# STM32_Sheet.net
KiCad netlist of a schematic drawn in Altium Designer
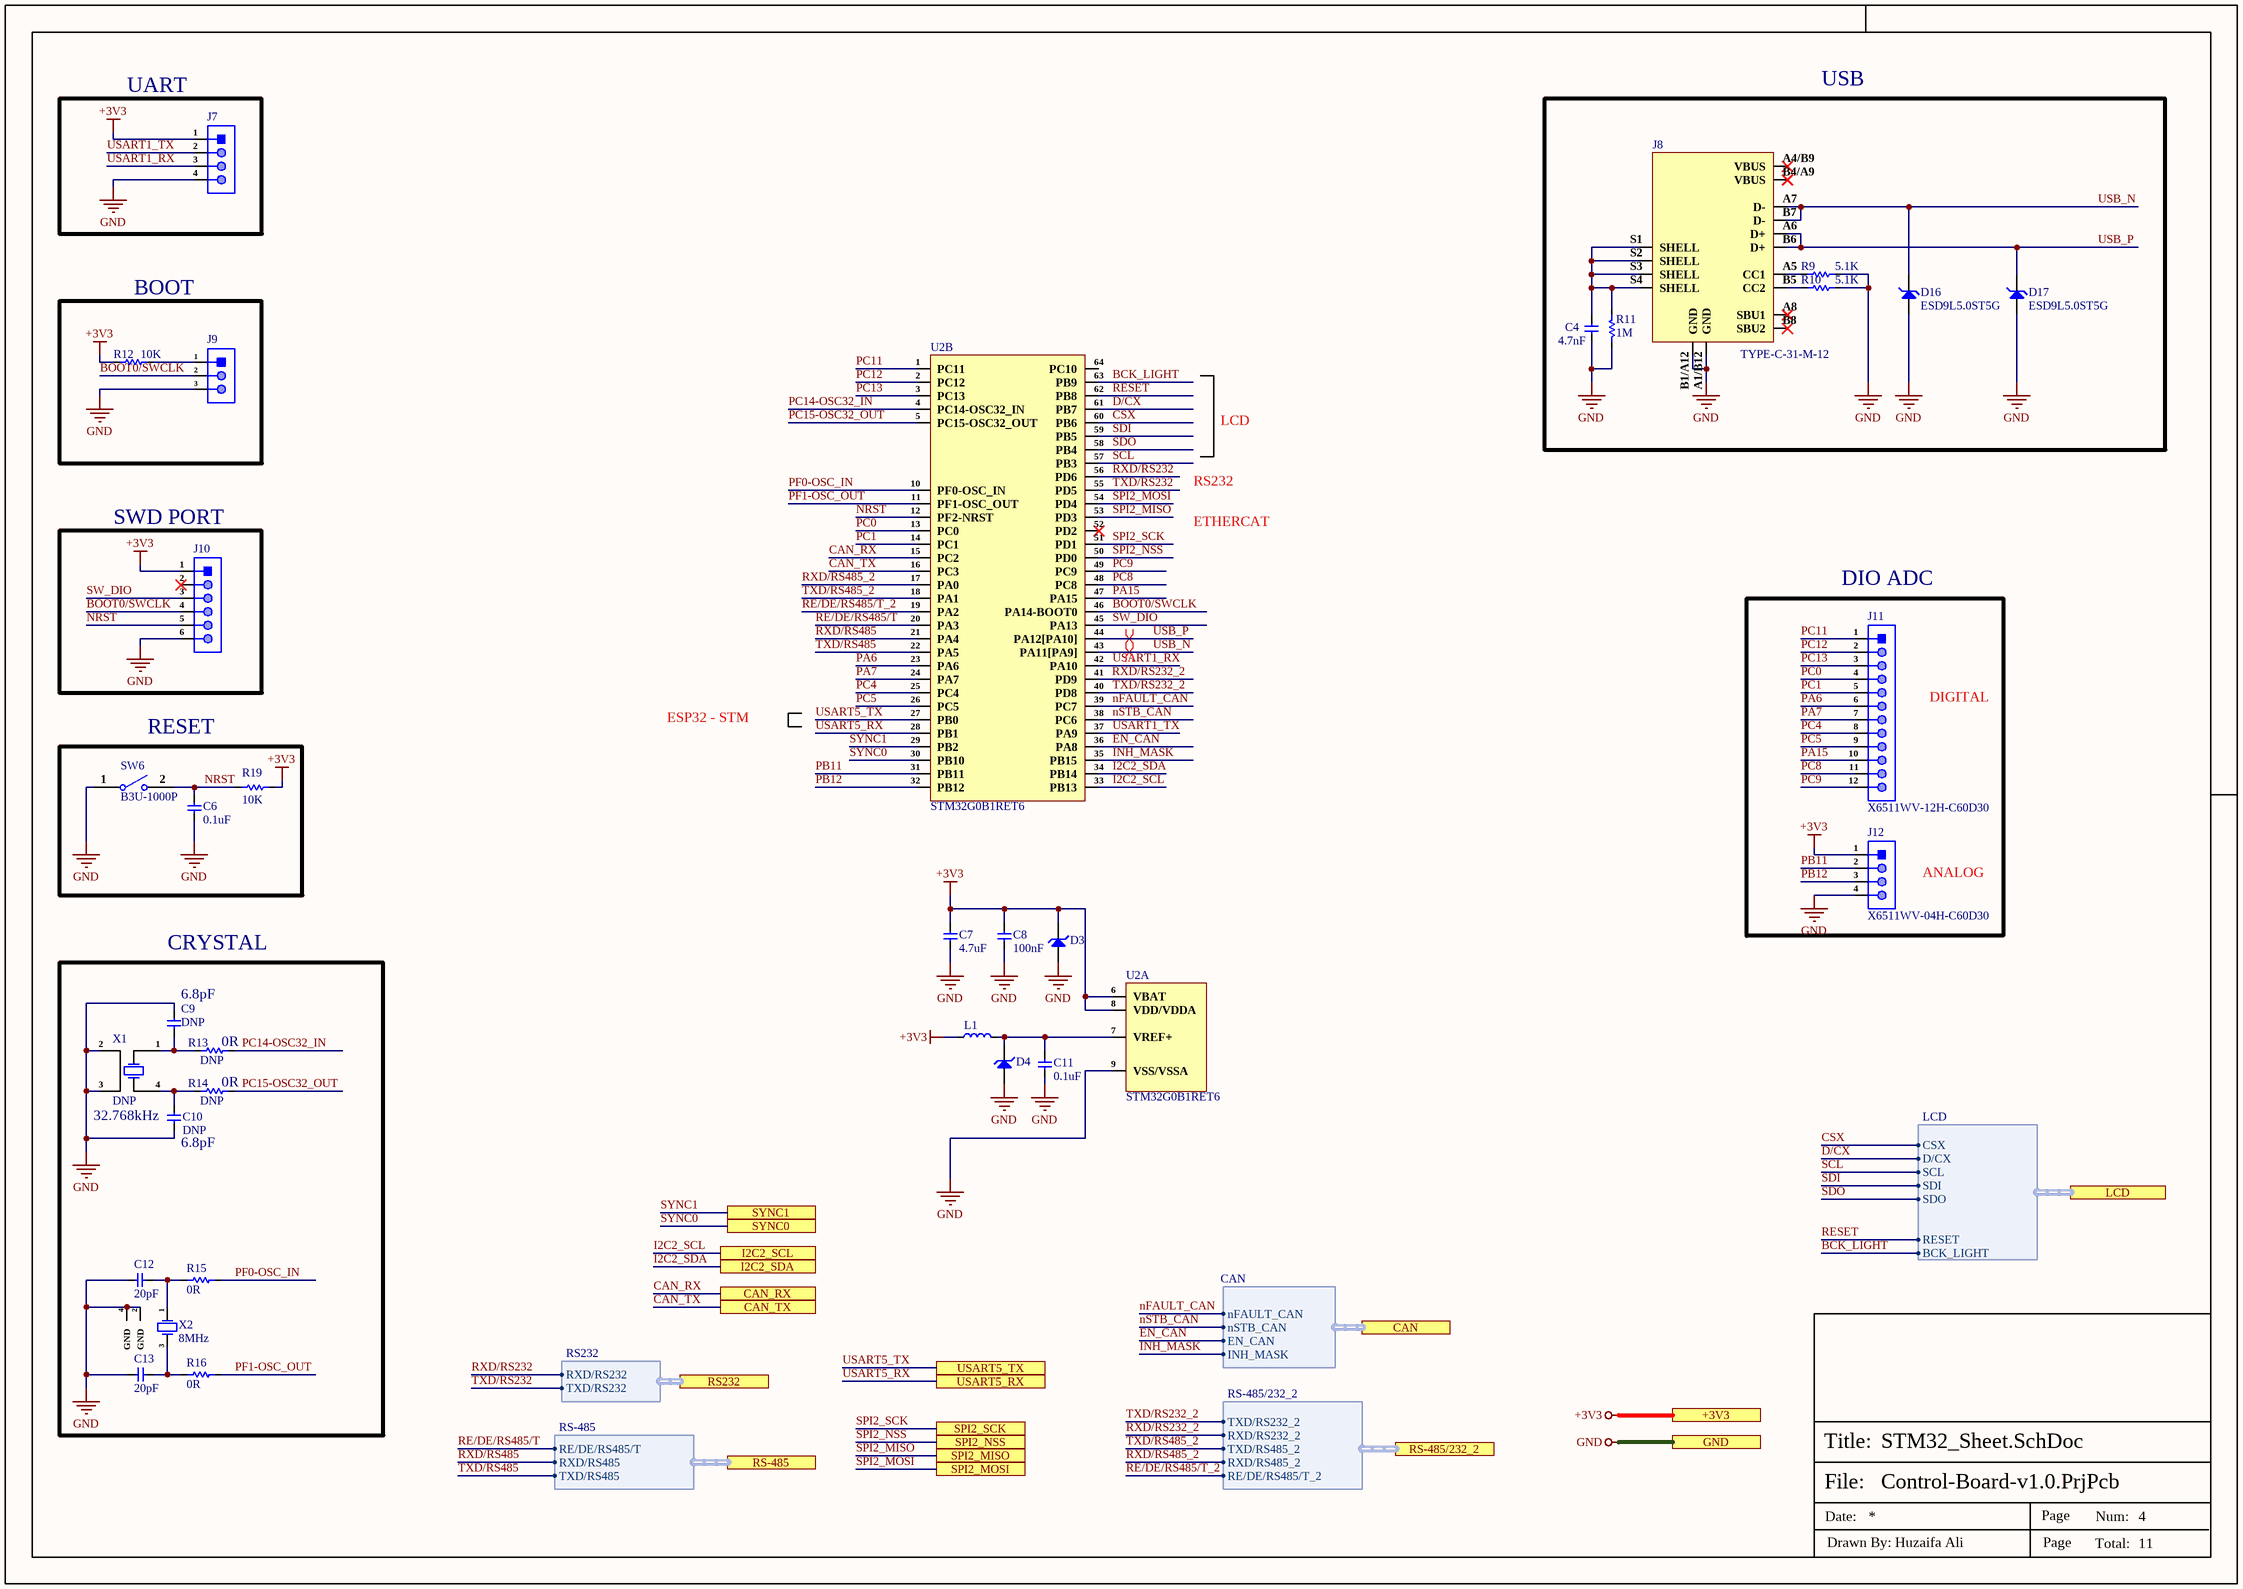
[diagram p0: STM32_Sheet.SchDoc]

(export (version "E")
  (design (tool "Eeschema 10.0.6"))
  (components
    (comp (ref "C4")
      (value "4.7nF")
      (footprint "Cap-0603")
      (description "CAP CER 4700PF 50V C0G/NPO 0603")
      (fields
        (field (name "MANUFACTURER") "Yageo")
        (field (name "MANUFACTURER PART NUMBER") "CC0603JRNPO9BN472")
      )
      (libsource (lib "eSpark_centralized_Library(2022)") (part "CC0603JRNPO9BN472"))
    )
    (comp (ref "C6")
      (value "0.1uF")
      (footprint "Cap-0402")
      (description "CAP CER 0.1UF 16V X7R 0402")
      (fields
        (field (name "MANUFACTURER") "Yageo")
        (field (name "MANUFACTURER PART NUMBER") "CC0402JRX7R7BB104")
      )
      (libsource (lib "eSpark Libraries") (part "CC0402JRX7R7BB104"))
    )
    (comp (ref "C7")
      (value "4.7uF")
      (footprint "Cap-0402")
      (description "CAP CER 4.7UF 10V X5R 0402")
      (fields
        (field (name "MANUFACTURER") "Yageo")
        (field (name "MANUFACTURER PART NUMBER") "CC0402KRX5R6BB475")
      )
      (libsource (lib "eSpark Libraries") (part "CC0402KRX5R6BB475"))
    )
    (comp (ref "C8")
      (value "100nF")
      (footprint "cap-0402")
      (description "CAP CER 0.1UF 50V X7R 0402")
      (fields
        (field (name "MANUFACTURER") "TDK")
        (field (name "MANUFACTURER PART NUMBER") "C1005X7R1H104KT000F")
      )
      (libsource (lib "eSpark Libraries") (part "C1005X7R1H104KT000F"))
    )
    (comp (ref "C9")
      (value "DNP")
      (footprint "Cap-0402")
      (description "CAP CER 6.8PF 50V C0G/NPO 0402")
      (fields
        (field (name "MANUFACTURER") "Yageo")
        (field (name "MANUFACTURER PART NUMBER") "CC0402CRNPO9BN6R8")
      )
      (libsource (lib "eSpark Libraries") (part "CC0402CRNPO9BN6R8"))
    )
    (comp (ref "C10")
      (value "DNP")
      (footprint "Cap-0402")
      (description "CAP CER 6.8PF 50V C0G/NPO 0402")
      (fields
        (field (name "MANUFACTURER") "Yageo")
        (field (name "MANUFACTURER PART NUMBER") "CC0402CRNPO9BN6R8")
      )
      (libsource (lib "eSpark Libraries") (part "CC0402CRNPO9BN6R8"))
    )
    (comp (ref "C11")
      (value "0.1uF")
      (footprint "Cap-0402")
      (description "CAP CER 0.1UF 16V X7R 0402")
      (fields
        (field (name "MANUFACTURER") "Yageo")
        (field (name "MANUFACTURER PART NUMBER") "CC0402JRX7R7BB104")
      )
      (libsource (lib "eSpark Libraries") (part "CC0402JRX7R7BB104"))
    )
    (comp (ref "C12")
      (value "20pF")
      (footprint "Cap-0402")
      (description "CAP CER 20PF 50V C0G/NPO 0402")
      (fields (field (name "LCSC PART NUMBER") "C107000") (field (name "MANUFACTURER") "Yageo"))
      (libsource (lib "eSpark Libraries") (part "CC0402JRNPO9BN200"))
    )
    (comp (ref "C13")
      (value "20pF")
      (footprint "Cap-0402")
      (description "CAP CER 20PF 50V C0G/NPO 0402")
      (fields (field (name "LCSC PART NUMBER") "C107000") (field (name "MANUFACTURER") "Yageo"))
      (libsource (lib "eSpark Libraries") (part "CC0402JRNPO9BN200"))
    )
    (comp (ref "D3")
      (value "AZ3003-01G")
      (footprint "SOD-123")
      (description "TVS SURGE PROTECTOR 1-CH 3.3V")
      (fields (field (name "MANUFACTURER") "Amazing"))
      (libsource (lib "eSpark Libraries") (part "AZ3003-01G"))
    )
    (comp (ref "D4")
      (value "AZ3003-01G")
      (footprint "SOD-123")
      (description "TVS SURGE PROTECTOR 1-CH 3.3V")
      (fields (field (name "MANUFACTURER") "Amazing"))
      (libsource (lib "eSpark Libraries") (part "AZ3003-01G"))
    )
    (comp (ref "D16")
      (value "ESD9L5.0ST5G")
      (footprint "SOD-923.")
      (description "TVS DIODE 5V 9.8V SOD923")
      (fields (field (name "MANUFACTURER") "ON Semiconductor") (field (name "LCSC PART NUMBER") "C82326"))
      (libsource (lib "eSpark Libraries") (part "ESD9L5.0ST5G"))
    )
    (comp (ref "D17")
      (value "ESD9L5.0ST5G")
      (footprint "SOD-923.")
      (description "TVS DIODE 5V 9.8V SOD923")
      (fields (field (name "MANUFACTURER") "ON Semiconductor") (field (name "LCSC PART NUMBER") "C82326"))
      (libsource (lib "eSpark Libraries") (part "ESD9L5.0ST5G"))
    )
    (comp (ref "J7")
      (value "X6511WV-04H-C60D30")
      (footprint "HDR1X4_")
      (fields (field (name "MANUFACTURER") "XKB") (field (name "LCSC PART NUMBER") "C706876"))
      (libsource (lib "eSpark Libraries") (part "X6511WV-04H-C60D30"))
    )
    (comp (ref "J8")
      (value "TYPE-C-31-M-12")
      (footprint "TYPE-C-31-M-12_")
      (description "5A 1 16P Female Type-C SMD USB Connectors ROHS")
      (fields
        (field (name "MANUFACTURER") "Korean Hroparts Elec")
        (field (name "LCSC PART NUMBER") "C165948")
      )
      (libsource (lib "eSpark Libraries") (part "TYPE-C-31-M-12"))
    )
    (comp (ref "J9")
      (value "68000-103HLF")
      (footprint "HDR1X3_")
      (description "CONN HEADER VERT 3POS 2.54MM")
      (fields (field (name "LCSC PART NUMBER") "C168677"))
      (libsource (lib "eSpark Libraries") (part "68000-103HLF"))
    )
    (comp (ref "J10")
      (value "X6511WV-06H-C60D30")
      (footprint "HDR1X6_")
      (fields (field (name "MANUFACTURER") "XKB") (field (name "LCSC PART NUMBER") "C706878"))
      (libsource (lib "eSpark Libraries") (part "X6511WV-06H-C60D30"))
    )
    (comp (ref "J11")
      (value "X6511WV-12H-C60D30")
      (footprint "HDR 1x12 TH")
      (fields (field (name "MANUFACTURER") "XKB") (field (name "LCSC PART NUMBER") "C725944"))
      (libsource (lib "eSpark Libraries") (part "X6511WV-12H-C60D30"))
    )
    (comp (ref "J12")
      (value "X6511WV-04H-C60D30")
      (footprint "HDR1X4_")
      (fields (field (name "MANUFACTURER") "XKB") (field (name "LCSC PART NUMBER") "C706876"))
      (libsource (lib "eSpark Libraries") (part "X6511WV-04H-C60D30"))
    )
    (comp (ref "L1")
      (value "BLM15AG601SN1D")
      (footprint "IND-0402")
      (description "FERRITE BEAD 600 OHM 0402 1LN")
      (fields (field (name "MANUFACTURER") "Murata") (field (name "TOLERANCE") "25%"))
      (libsource (lib "eSpark Libraries") (part "BLM15AG601SN1D"))
    )
    (comp (ref "R9")
      (value "5.1K")
      (footprint "Res-0402")
      (description "RES 5.1K OHM 1% 1/16W 0402")
      (fields
        (field (name "MANUFACTURER") "Yageo")
        (field (name "MANUFACTURER PART NUMBER") "RC0402FR-075K1L")
      )
      (libsource (lib "eSpark Libraries") (part "RC0402FR-075K1L"))
    )
    (comp (ref "R10")
      (value "5.1K")
      (footprint "Res-0402")
      (description "RES 5.1K OHM 1% 1/16W 0402")
      (fields
        (field (name "MANUFACTURER") "Yageo")
        (field (name "MANUFACTURER PART NUMBER") "RC0402FR-075K1L")
      )
      (libsource (lib "eSpark Libraries") (part "RC0402FR-075K1L"))
    )
    (comp (ref "R11")
      (value "1M")
      (footprint "Res-0402")
      (description "RES SMD 1M OHM 5% 1/16W 0402")
      (fields
        (field (name "MANUFACTURER") "Yageo")
        (field (name "MANUFACTURER PART NUMBER") "AF0402JR-071ML")
      )
      (libsource (lib "eSpark_centralized_Library(2022)") (part "AF0402JR-071ML"))
    )
    (comp (ref "R12")
      (value "10K")
      (footprint "Res-0402")
      (description "RES 10K OHM 1% 1/16W 0402")
      (fields
        (field (name "MANUFACTURER") "Yageo")
        (field (name "MANUFACTURER PART NUMBER") "RC0402FR-0710KL")
      )
      (libsource (lib "eSpark Libraries") (part "RC0402FR-0710KL"))
    )
    (comp (ref "R13")
      (value "DNP")
      (footprint "Res-0603")
      (description "RES 0 OHM JUMPER 1/10W 0603")
      (fields
        (field (name "MANUFACTURER") "Yageo")
        (field (name "MANUFACTURER PART NUMBER") "RC0603JR-070RL")
      )
      (libsource (lib "eSpark Libraries") (part "RC0603JR-070RL"))
    )
    (comp (ref "R14")
      (value "DNP")
      (footprint "Res-0603")
      (description "RES 0 OHM JUMPER 1/10W 0603")
      (fields
        (field (name "MANUFACTURER") "Yageo")
        (field (name "MANUFACTURER PART NUMBER") "RC0603JR-070RL")
      )
      (libsource (lib "eSpark Libraries") (part "RC0603JR-070RL"))
    )
    (comp (ref "R15")
      (value "0R")
      (footprint "Res-0603")
      (description "RES 0 OHM JUMPER 1/10W 0603")
      (fields
        (field (name "MANUFACTURER") "Yageo")
        (field (name "MANUFACTURER PART NUMBER") "RC0603JR-070RL")
      )
      (libsource (lib "eSpark Libraries") (part "RC0603JR-070RL"))
    )
    (comp (ref "R16")
      (value "0R")
      (footprint "Res-0603")
      (description "RES 0 OHM JUMPER 1/10W 0603")
      (fields
        (field (name "MANUFACTURER") "Yageo")
        (field (name "MANUFACTURER PART NUMBER") "RC0603JR-070RL")
      )
      (libsource (lib "eSpark Libraries") (part "RC0603JR-070RL"))
    )
    (comp (ref "R19")
      (value "10K")
      (footprint "Res-0402")
      (description "RES 10K OHM 1% 1/16W 0402")
      (fields
        (field (name "MANUFACTURER") "Yageo")
        (field (name "MANUFACTURER PART NUMBER") "RC0402FR-0710KL")
      )
      (libsource (lib "eSpark Libraries") (part "RC0402FR-0710KL"))
    )
    (comp (ref "SW6")
      (value "B3U-1000P")
      (footprint "B3U-1000P")
      (description "SWITCH TACTILE SPST-NO 0.05A 12V")
      (fields (field (name "MANUFACTURER") "Omron") (field (name "LCSC PART NUMBER") "C231329"))
      (libsource (lib "eSpark Libraries") (part "B3U-1000P"))
    )
    (comp (ref "U2")
      (value "STM32G0B1RET6")
      (footprint "LQFP-64(10x10)")
      (description "IC MCU 32BIT 512KB FLASH 64LQFP")
      (fields (field (name "MANUFACTURER") "STMicroelectronics") (field (name "LCSC PART NUMBER") "C2829307"))
      (libsource (lib "eSpark Libraries") (part "STM32G0B1RET6"))
    )
    (comp (ref "X1")
      (value "DNP")
      (footprint "MC-306")
      (description "32.768kHz 12.5pF ±20ppm MC-306 Crystals ROHS")
      (fields
        (field (name "MANUFACTURER") "Seiko Epson")
        (field (name "MANUFACTURER PART NUMBER") "MC-306 32.7680K-A0:ROHS")
      )
      (libsource (lib "eSpark Libraries") (part "MC-306 32.7680K-A0{colon}ROHS"))
    )
    (comp (ref "X2")
      (value "8MHz")
      (footprint "5TJ480000XYLBC_")
      (description "8MHz 18pF ±10ppm SMD5032-4P Crystals ROHS")
      (fields (field (name "MANUFACTURER") "JYJE") (field (name "MANUFACTURER PART NUMBER") "5TJ480000XYLBC"))
      (libsource (lib "eSpark Libraries") (part "5TJ480000XYLBC"))
    )
  )
  (nets
    (net (code "6") (name "+3V3") (class "Default")
      (node (ref "C7") (pin "2") (pinfunction "2_2") (pintype "passive"))
      (node (ref "C8") (pin "2") (pinfunction "2_2") (pintype "passive"))
      (node (ref "D3") (pin "2") (pinfunction "K_2") (pintype "passive"))
      (node (ref "J10") (pin "1") (pinfunction "1_1") (pintype "passive"))
      (node (ref "J12") (pin "1") (pinfunction "1_1") (pintype "passive"))
      (node (ref "J7") (pin "1") (pinfunction "1_1") (pintype "passive"))
      (node (ref "L1") (pin "1") (pinfunction "1_1") (pintype "passive"))
      (node (ref "R12") (pin "2") (pinfunction "2_2") (pintype "passive"))
      (node (ref "R19") (pin "2") (pinfunction "2_2") (pintype "passive"))
      (node (ref "U2") (pin "6") (pinfunction "VBAT_6") (pintype "passive"))
      (node (ref "U2") (pin "8") (pinfunction "VDD/VDDA_8") (pintype "passive"))
    )
    (net (code "7") (name "/BCK_LIGHT") (class "Default")
      (node (ref "U2") (pin "63") (pinfunction "PB9_63") (pintype "passive"))
    )
    (net (code "8") (name "/BOOT0{slash}SWCLK") (class "Default")
      (node (ref "J10") (pin "4") (pinfunction "4_4") (pintype "passive"))
      (node (ref "J9") (pin "2") (pinfunction "2_2") (pintype "passive"))
      (node (ref "U2") (pin "46") (pinfunction "PA14-BOOT0_46") (pintype "passive"))
    )
    (net (code "9") (name "/CAN_RX") (class "Default")
      (node (ref "U2") (pin "15") (pinfunction "PC2_15") (pintype "passive"))
    )
    (net (code "10") (name "/CAN_TX") (class "Default")
      (node (ref "U2") (pin "16") (pinfunction "PC3_16") (pintype "passive"))
    )
    (net (code "11") (name "/CSX") (class "Default")
      (node (ref "U2") (pin "60") (pinfunction "PB6_60") (pintype "passive"))
    )
    (net (code "12") (name "/D{slash}CX") (class "Default")
      (node (ref "U2") (pin "61") (pinfunction "PB7_61") (pintype "passive"))
    )
    (net (code "13") (name "/EN_CAN") (class "Default")
      (node (ref "U2") (pin "36") (pinfunction "PA8_36") (pintype "passive"))
    )
    (net (code "14") (name "/I2C2_SCL") (class "Default")
      (node (ref "U2") (pin "33") (pinfunction "PB13_33") (pintype "passive"))
    )
    (net (code "15") (name "/I2C2_SDA") (class "Default")
      (node (ref "U2") (pin "34") (pinfunction "PB14_34") (pintype "passive"))
    )
    (net (code "16") (name "/INH_MASK") (class "Default")
      (node (ref "U2") (pin "35") (pinfunction "PB15_35") (pintype "passive"))
    )
    (net (code "17") (name "/NRST") (class "Default")
      (node (ref "C6") (pin "2") (pinfunction "2_2") (pintype "passive"))
      (node (ref "J10") (pin "5") (pinfunction "5_5") (pintype "passive"))
      (node (ref "R19") (pin "1") (pinfunction "1_1") (pintype "passive"))
      (node (ref "SW6") (pin "2") (pinfunction "2_2") (pintype "passive"))
      (node (ref "U2") (pin "12") (pinfunction "PF2-NRST_12") (pintype "passive"))
    )
    (net (code "18") (name "/PA6") (class "Default")
      (node (ref "J11") (pin "6") (pinfunction "6_6") (pintype "passive"))
      (node (ref "U2") (pin "23") (pinfunction "PA6_23") (pintype "passive"))
    )
    (net (code "19") (name "/PA7") (class "Default")
      (node (ref "J11") (pin "7") (pinfunction "7_7") (pintype "passive"))
      (node (ref "U2") (pin "24") (pinfunction "PA7_24") (pintype "passive"))
    )
    (net (code "20") (name "/PA15") (class "Default")
      (node (ref "J11") (pin "10") (pinfunction "10_10") (pintype "passive"))
      (node (ref "U2") (pin "47") (pinfunction "PA15_47") (pintype "passive"))
    )
    (net (code "21") (name "/PB11") (class "Default")
      (node (ref "J12") (pin "2") (pinfunction "2_2") (pintype "passive"))
      (node (ref "U2") (pin "31") (pinfunction "PB11_31") (pintype "passive"))
    )
    (net (code "22") (name "/PB12") (class "Default")
      (node (ref "J12") (pin "3") (pinfunction "3_3") (pintype "passive"))
      (node (ref "U2") (pin "32") (pinfunction "PB12_32") (pintype "passive"))
    )
    (net (code "23") (name "/PC0") (class "Default")
      (node (ref "J11") (pin "4") (pinfunction "4_4") (pintype "passive"))
      (node (ref "U2") (pin "13") (pinfunction "PC0_13") (pintype "passive"))
    )
    (net (code "24") (name "/PC1") (class "Default")
      (node (ref "J11") (pin "5") (pinfunction "5_5") (pintype "passive"))
      (node (ref "U2") (pin "14") (pinfunction "PC1_14") (pintype "passive"))
    )
    (net (code "25") (name "/PC4") (class "Default")
      (node (ref "J11") (pin "8") (pinfunction "8_8") (pintype "passive"))
      (node (ref "U2") (pin "25") (pinfunction "PC4_25") (pintype "passive"))
    )
    (net (code "26") (name "/PC5") (class "Default")
      (node (ref "J11") (pin "9") (pinfunction "9_9") (pintype "passive"))
      (node (ref "U2") (pin "26") (pinfunction "PC5_26") (pintype "passive"))
    )
    (net (code "27") (name "/PC8") (class "Default")
      (node (ref "J11") (pin "11") (pinfunction "11_11") (pintype "passive"))
      (node (ref "U2") (pin "48") (pinfunction "PC8_48") (pintype "passive"))
    )
    (net (code "28") (name "/PC9") (class "Default")
      (node (ref "J11") (pin "12") (pinfunction "12_12") (pintype "passive"))
      (node (ref "U2") (pin "49") (pinfunction "PC9_49") (pintype "passive"))
    )
    (net (code "29") (name "/PC11") (class "Default")
      (node (ref "J11") (pin "1") (pinfunction "1_1") (pintype "passive"))
      (node (ref "U2") (pin "1") (pinfunction "PC11_1") (pintype "passive"))
    )
    (net (code "30") (name "/PC12") (class "Default")
      (node (ref "J11") (pin "2") (pinfunction "2_2") (pintype "passive"))
      (node (ref "U2") (pin "2") (pinfunction "PC12_2") (pintype "passive"))
    )
    (net (code "31") (name "/PC13") (class "Default")
      (node (ref "J11") (pin "3") (pinfunction "3_3") (pintype "passive"))
      (node (ref "U2") (pin "3") (pinfunction "PC13_3") (pintype "passive"))
    )
    (net (code "32") (name "/PC14-OSC32_IN") (class "Default")
      (node (ref "R13") (pin "2") (pinfunction "2_2") (pintype "passive"))
      (node (ref "U2") (pin "4") (pinfunction "PC14-OSC32_IN_4") (pintype "passive"))
    )
    (net (code "33") (name "/PC15-OSC32_OUT") (class "Default")
      (node (ref "R14") (pin "2") (pinfunction "2_2") (pintype "passive"))
      (node (ref "U2") (pin "5") (pinfunction "PC15-OSC32_OUT_5") (pintype "passive"))
    )
    (net (code "34") (name "/PF0-OSC_IN") (class "Default")
      (node (ref "R15") (pin "2") (pinfunction "2_2") (pintype "passive"))
      (node (ref "U2") (pin "10") (pinfunction "PF0-OSC_IN_10") (pintype "passive"))
    )
    (net (code "35") (name "/PF1-OSC_OUT") (class "Default")
      (node (ref "R16") (pin "2") (pinfunction "2_2") (pintype "passive"))
      (node (ref "U2") (pin "11") (pinfunction "PF1-OSC_OUT_11") (pintype "passive"))
    )
    (net (code "36") (name "/RESET") (class "Default")
      (node (ref "U2") (pin "62") (pinfunction "PB8_62") (pintype "passive"))
    )
    (net (code "37") (name "/RE{slash}DE{slash}RS485{slash}T") (class "Default")
      (node (ref "U2") (pin "20") (pinfunction "PA3_20") (pintype "passive"))
    )
    (net (code "38") (name "/RE{slash}DE{slash}RS485{slash}T_2") (class "Default")
      (node (ref "U2") (pin "19") (pinfunction "PA2_19") (pintype "passive"))
    )
    (net (code "39") (name "/RXD{slash}RS232") (class "Default")
      (node (ref "U2") (pin "56") (pinfunction "PD6_56") (pintype "passive"))
    )
    (net (code "40") (name "/RXD{slash}RS232_2") (class "Default")
      (node (ref "U2") (pin "41") (pinfunction "PD9_41") (pintype "passive"))
    )
    (net (code "41") (name "/RXD{slash}RS485") (class "Default")
      (node (ref "U2") (pin "21") (pinfunction "PA4_21") (pintype "passive"))
    )
    (net (code "42") (name "/RXD{slash}RS485_2") (class "Default")
      (node (ref "U2") (pin "17") (pinfunction "PA0_17") (pintype "passive"))
    )
    (net (code "43") (name "/SCL") (class "Default")
      (node (ref "U2") (pin "57") (pinfunction "PB3_57") (pintype "passive"))
    )
    (net (code "44") (name "/SDI") (class "Default")
      (node (ref "U2") (pin "59") (pinfunction "PB5_59") (pintype "passive"))
    )
    (net (code "45") (name "/SDO") (class "Default")
      (node (ref "U2") (pin "58") (pinfunction "PB4_58") (pintype "passive"))
    )
    (net (code "46") (name "/SPI2_MISO") (class "Default")
      (node (ref "U2") (pin "53") (pinfunction "PD3_53") (pintype "passive"))
    )
    (net (code "47") (name "/SPI2_MOSI") (class "Default")
      (node (ref "U2") (pin "54") (pinfunction "PD4_54") (pintype "passive"))
    )
    (net (code "48") (name "/SPI2_NSS") (class "Default")
      (node (ref "U2") (pin "50") (pinfunction "PD0_50") (pintype "passive"))
    )
    (net (code "49") (name "/SPI2_SCK") (class "Default")
      (node (ref "U2") (pin "51") (pinfunction "PD1_51") (pintype "passive"))
    )
    (net (code "50") (name "/SW_DIO") (class "Default")
      (node (ref "J10") (pin "3") (pinfunction "3_3") (pintype "passive"))
      (node (ref "U2") (pin "45") (pinfunction "PA13_45") (pintype "passive"))
    )
    (net (code "51") (name "/SYNC0") (class "Default")
      (node (ref "U2") (pin "30") (pinfunction "PB10_30") (pintype "passive"))
    )
    (net (code "52") (name "/SYNC1") (class "Default")
      (node (ref "U2") (pin "29") (pinfunction "PB2_29") (pintype "passive"))
    )
    (net (code "53") (name "/TXD{slash}RS232") (class "Default")
      (node (ref "U2") (pin "55") (pinfunction "PD5_55") (pintype "passive"))
    )
    (net (code "54") (name "/TXD{slash}RS232_2") (class "Default")
      (node (ref "U2") (pin "40") (pinfunction "PD8_40") (pintype "passive"))
    )
    (net (code "55") (name "/TXD{slash}RS485") (class "Default")
      (node (ref "U2") (pin "22") (pinfunction "PA5_22") (pintype "passive"))
    )
    (net (code "56") (name "/TXD{slash}RS485_2") (class "Default")
      (node (ref "U2") (pin "18") (pinfunction "PA1_18") (pintype "passive"))
    )
    (net (code "57") (name "/USART1_RX") (class "Default")
      (node (ref "J7") (pin "3") (pinfunction "3_3") (pintype "passive"))
      (node (ref "U2") (pin "42") (pinfunction "PA10_42") (pintype "passive"))
    )
    (net (code "58") (name "/USART1_TX") (class "Default")
      (node (ref "J7") (pin "2") (pinfunction "2_2") (pintype "passive"))
      (node (ref "U2") (pin "37") (pinfunction "PA9_37") (pintype "passive"))
    )
    (net (code "59") (name "/USART5_RX") (class "Default")
      (node (ref "U2") (pin "28") (pinfunction "PB1_28") (pintype "passive"))
    )
    (net (code "60") (name "/USART5_TX") (class "Default")
      (node (ref "U2") (pin "27") (pinfunction "PB0_27") (pintype "passive"))
    )
    (net (code "61") (name "/USB_N") (class "Default")
      (node (ref "D16") (pin "1") (pinfunction "K_1") (pintype "passive"))
      (node (ref "J8") (pin "A7") (pinfunction "D-_A7") (pintype "passive"))
      (node (ref "J8") (pin "B7") (pinfunction "D-_B7") (pintype "passive"))
      (node (ref "U2") (pin "43") (pinfunction "PA11[PA9]_43") (pintype "passive"))
    )
    (net (code "62") (name "/USB_P") (class "Default")
      (node (ref "D17") (pin "1") (pinfunction "K_1") (pintype "passive"))
      (node (ref "J8") (pin "A6") (pinfunction "D+_A6") (pintype "passive"))
      (node (ref "J8") (pin "B6") (pinfunction "D+_B6") (pintype "passive"))
      (node (ref "U2") (pin "44") (pinfunction "PA12[PA10]_44") (pintype "passive"))
    )
    (net (code "63") (name "/nFAULT_CAN") (class "Default")
      (node (ref "U2") (pin "39") (pinfunction "PC7_39") (pintype "passive"))
    )
    (net (code "64") (name "/nSTB_CAN") (class "Default")
      (node (ref "U2") (pin "38") (pinfunction "PC6_38") (pintype "passive"))
    )
    (net (code "70") (name "GND") (class "Default")
      (node (ref "C10") (pin "2") (pinfunction "2_2") (pintype "passive"))
      (node (ref "C11") (pin "1") (pinfunction "1_1") (pintype "passive"))
      (node (ref "C12") (pin "1") (pinfunction "1_1") (pintype "passive"))
      (node (ref "C13") (pin "2") (pinfunction "2_2") (pintype "passive"))
      (node (ref "C4") (pin "1") (pinfunction "1_1") (pintype "passive"))
      (node (ref "C6") (pin "1") (pinfunction "1_1") (pintype "passive"))
      (node (ref "C7") (pin "1") (pinfunction "1_1") (pintype "passive"))
      (node (ref "C8") (pin "1") (pinfunction "1_1") (pintype "passive"))
      (node (ref "C9") (pin "1") (pinfunction "1_1") (pintype "passive"))
      (node (ref "D16") (pin "2") (pinfunction "A_2") (pintype "passive"))
      (node (ref "D17") (pin "2") (pinfunction "A_2") (pintype "passive"))
      (node (ref "D3") (pin "1") (pinfunction "A_1") (pintype "passive"))
      (node (ref "D4") (pin "1") (pinfunction "A_1") (pintype "passive"))
      (node (ref "J10") (pin "6") (pinfunction "6_6") (pintype "passive"))
      (node (ref "J12") (pin "4") (pinfunction "4_4") (pintype "passive"))
      (node (ref "J7") (pin "4") (pinfunction "4_4") (pintype "passive"))
      (node (ref "J8") (pin "A1/B12") (pinfunction "GND_A1/B12") (pintype "power_in"))
      (node (ref "J8") (pin "B1/A12") (pinfunction "GND_B1/A12") (pintype "power_in"))
      (node (ref "J9") (pin "3") (pinfunction "3_3") (pintype "passive"))
      (node (ref "R10") (pin "2") (pinfunction "2_2") (pintype "passive"))
      (node (ref "R11") (pin "2") (pinfunction "2_2") (pintype "passive"))
      (node (ref "R9") (pin "2") (pinfunction "2_2") (pintype "passive"))
      (node (ref "SW6") (pin "1") (pinfunction "1_1") (pintype "passive"))
      (node (ref "U2") (pin "9") (pinfunction "VSS/VSSA_9") (pintype "passive"))
      (node (ref "X1") (pin "2") (pinfunction "2_2") (pintype "passive"))
      (node (ref "X1") (pin "3") (pinfunction "3_3") (pintype "passive"))
      (node (ref "X2") (pin "2") (pinfunction "GND_2") (pintype "passive"))
      (node (ref "X2") (pin "4") (pinfunction "GND_4") (pintype "passive"))
    )
    (net (code "71") (name "Net-(C4-Pad2)") (class "Default")
      (node (ref "C4") (pin "2") (pinfunction "2_2") (pintype "passive"))
      (node (ref "J8") (pin "S1") (pinfunction "SHELL_S1") (pintype "passive"))
      (node (ref "J8") (pin "S2") (pinfunction "SHELL_S2") (pintype "passive"))
      (node (ref "J8") (pin "S3") (pinfunction "SHELL_S3") (pintype "passive"))
      (node (ref "J8") (pin "S4") (pinfunction "SHELL_S4") (pintype "passive"))
      (node (ref "R11") (pin "1") (pinfunction "1_1") (pintype "passive"))
    )
    (net (code "72") (name "Net-(D4-K)") (class "Default")
      (node (ref "C11") (pin "2") (pinfunction "2_2") (pintype "passive"))
      (node (ref "D4") (pin "2") (pinfunction "K_2") (pintype "passive"))
      (node (ref "L1") (pin "2") (pinfunction "2_2") (pintype "passive"))
      (node (ref "U2") (pin "7") (pinfunction "VREF+_7") (pintype "passive"))
    )
    (net (code "73") (name "Net-(J8-CC1)") (class "Default")
      (node (ref "J8") (pin "A5") (pinfunction "CC1_A5") (pintype "passive"))
      (node (ref "R9") (pin "1") (pinfunction "1_1") (pintype "passive"))
    )
    (net (code "74") (name "Net-(J8-CC2)") (class "Default")
      (node (ref "J8") (pin "B5") (pinfunction "CC2_B5") (pintype "passive"))
      (node (ref "R10") (pin "1") (pinfunction "1_1") (pintype "passive"))
    )
    (net (code "75") (name "Net-(J9-Pad1)") (class "Default")
      (node (ref "J9") (pin "1") (pinfunction "1_1") (pintype "passive"))
      (node (ref "R12") (pin "1") (pinfunction "1_1") (pintype "passive"))
    )
    (net (code "76") (name "Net-(X1-OSC1)") (class "Default")
      (node (ref "C9") (pin "2") (pinfunction "2_2") (pintype "passive"))
      (node (ref "R13") (pin "1") (pinfunction "1_1") (pintype "passive"))
      (node (ref "X1") (pin "1") (pinfunction "OSC1_1") (pintype "passive"))
    )
    (net (code "77") (name "Net-(X1-OSC2)") (class "Default")
      (node (ref "C10") (pin "1") (pinfunction "1_1") (pintype "passive"))
      (node (ref "R14") (pin "1") (pinfunction "1_1") (pintype "passive"))
      (node (ref "X1") (pin "4") (pinfunction "OSC2_4") (pintype "passive"))
    )
    (net (code "78") (name "Net-(X2-OSC1)") (class "Default")
      (node (ref "C12") (pin "2") (pinfunction "2_2") (pintype "passive"))
      (node (ref "R15") (pin "1") (pinfunction "1_1") (pintype "passive"))
      (node (ref "X2") (pin "1") (pinfunction "OSC1_1") (pintype "passive"))
    )
    (net (code "79") (name "Net-(X2-OSC2)") (class "Default")
      (node (ref "C13") (pin "1") (pinfunction "1_1") (pintype "passive"))
      (node (ref "R16") (pin "1") (pinfunction "1_1") (pintype "passive"))
      (node (ref "X2") (pin "3") (pinfunction "OSC2_3") (pintype "passive"))
    )
    (net (code "80") (name "unconnected-(J8-SBU1-PadA8)") (class "Default")
      (node (ref "J8") (pin "A8") (pinfunction "SBU1_A8") (pintype "passive+no_connect"))
    )
    (net (code "81") (name "unconnected-(J8-SBU2-PadB8)") (class "Default")
      (node (ref "J8") (pin "B8") (pinfunction "SBU2_B8") (pintype "passive+no_connect"))
    )
    (net (code "82") (name "unconnected-(J8-VBUS-PadA4{slash}B9)") (class "Default")
      (node (ref "J8") (pin "A4/B9") (pinfunction "VBUS_A4/B9") (pintype "power_in+no_connect"))
    )
    (net (code "83") (name "unconnected-(J8-VBUS-PadB4{slash}A9)") (class "Default")
      (node (ref "J8") (pin "B4/A9") (pinfunction "VBUS_B4/A9") (pintype "power_in+no_connect"))
    )
    (net (code "84") (name "unconnected-(J10-Pad2)") (class "Default")
      (node (ref "J10") (pin "2") (pinfunction "2_2") (pintype "passive+no_connect"))
    )
    (net (code "85") (name "unconnected-(U2B-PC10-Pad64)") (class "Default")
      (node (ref "U2") (pin "64") (pinfunction "PC10_64") (pintype "passive"))
    )
    (net (code "86") (name "unconnected-(U2B-PD2-Pad52)") (class "Default")
      (node (ref "U2") (pin "52") (pinfunction "PD2_52") (pintype "passive+no_connect"))
    )
  )
)
